# main.net
KiCad netlist of a schematic drawn in EAGLE
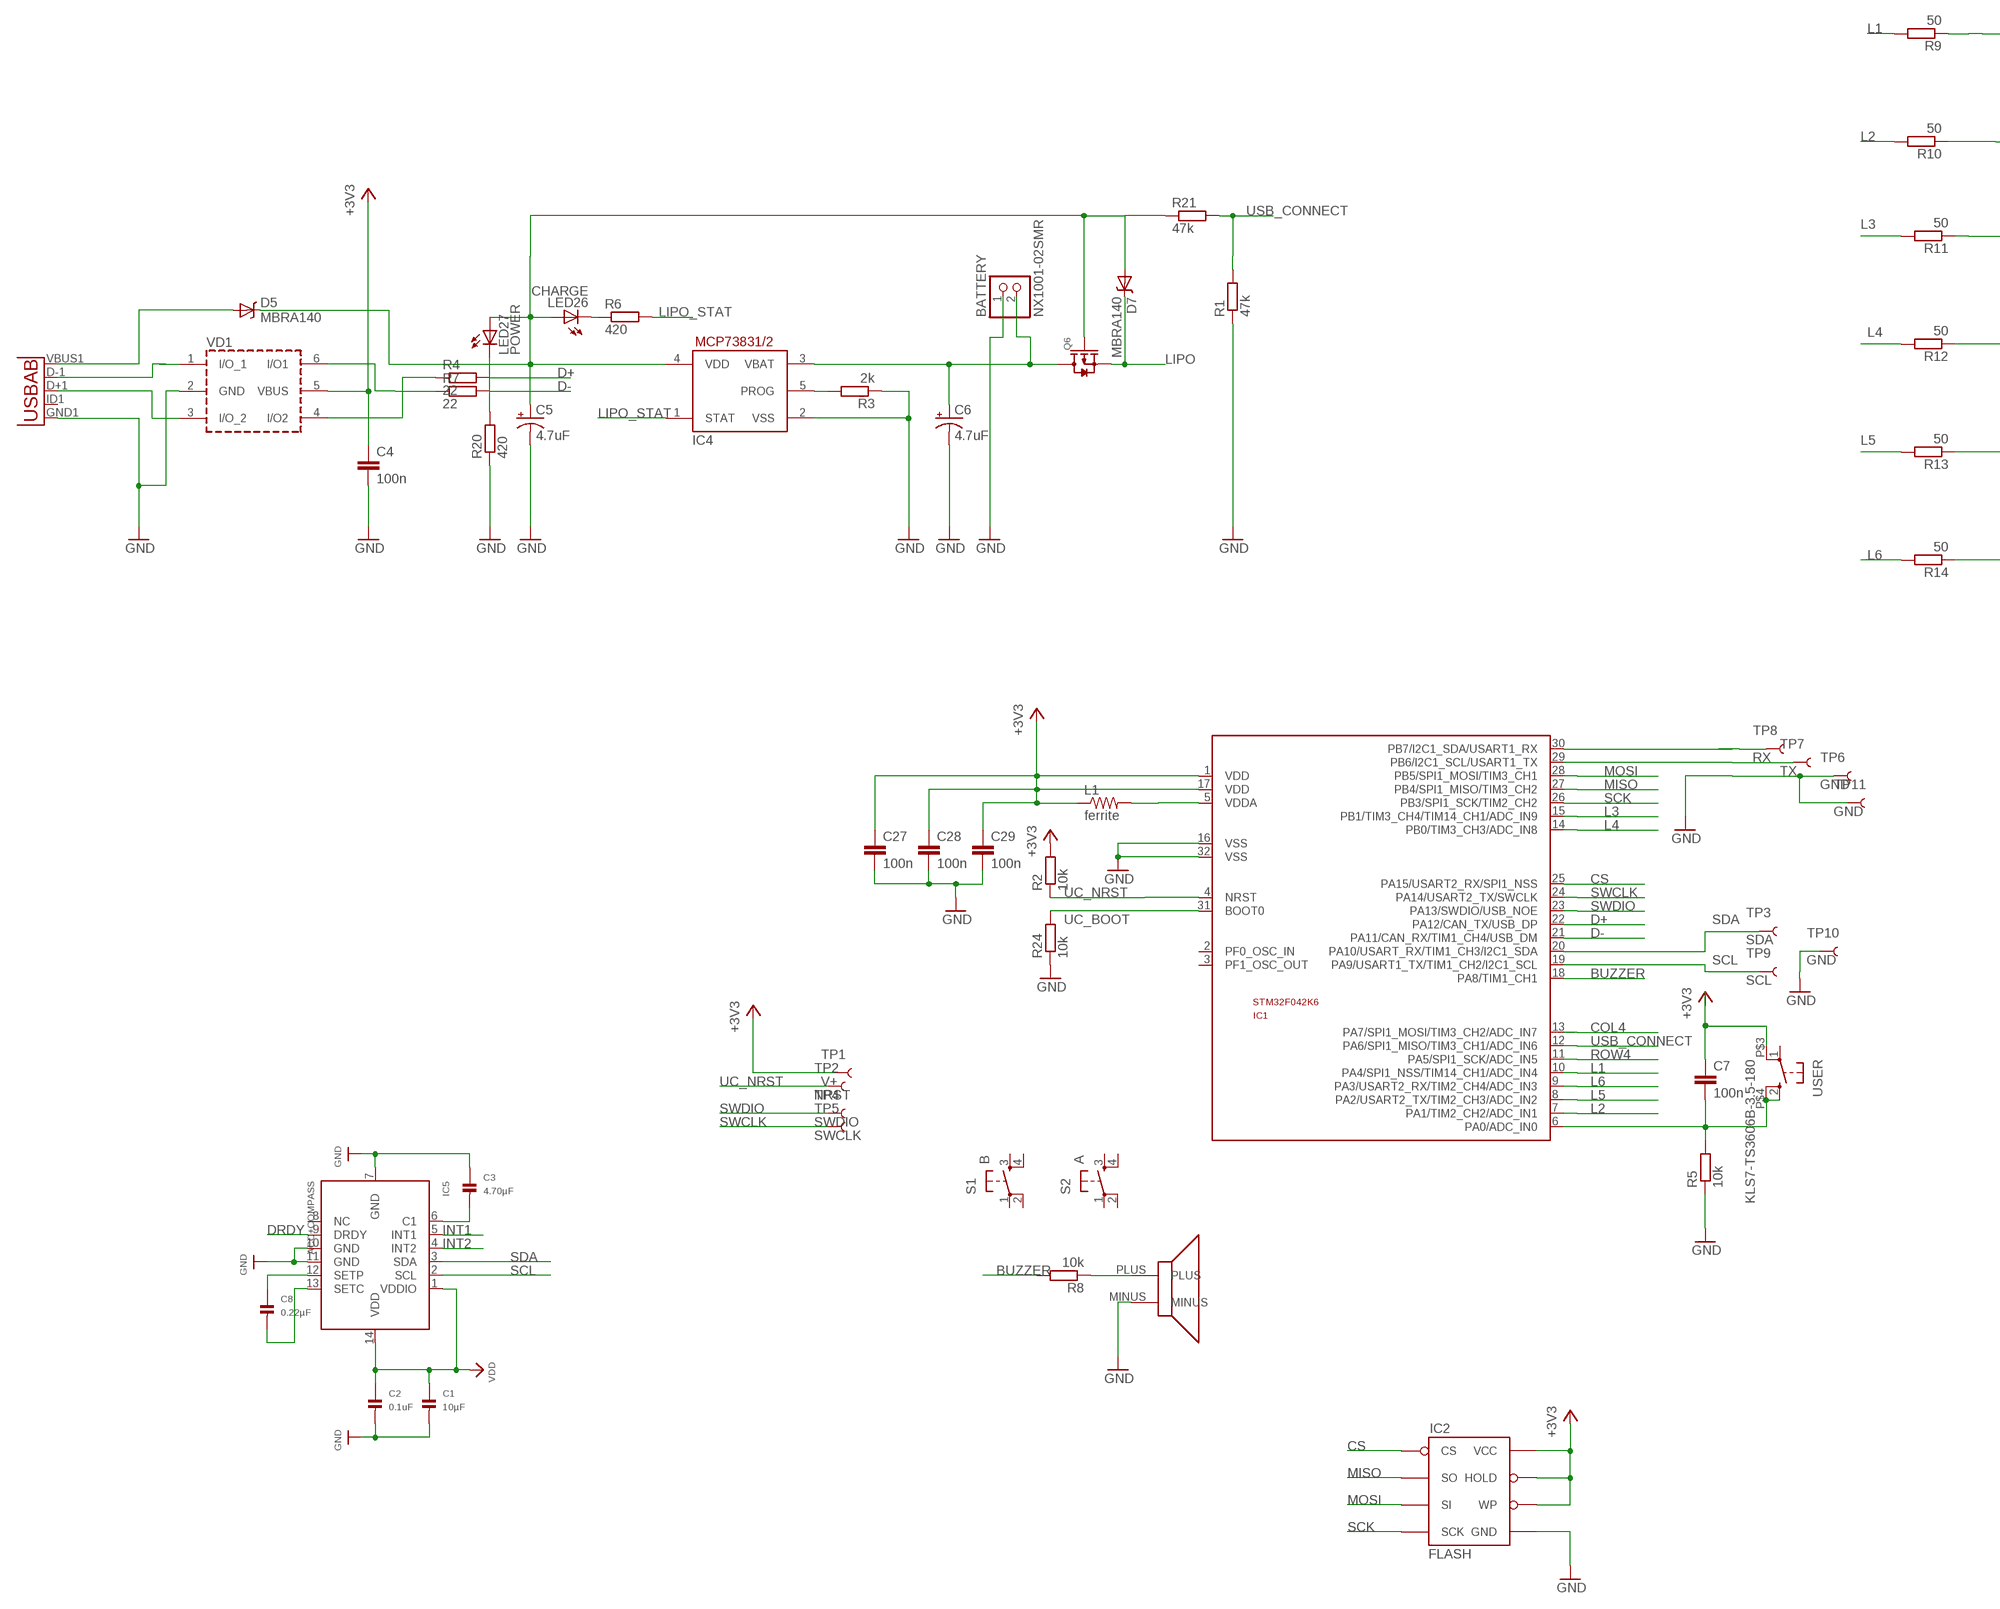
[diagram p0: schematic, sheet 1, part 1 of 2]
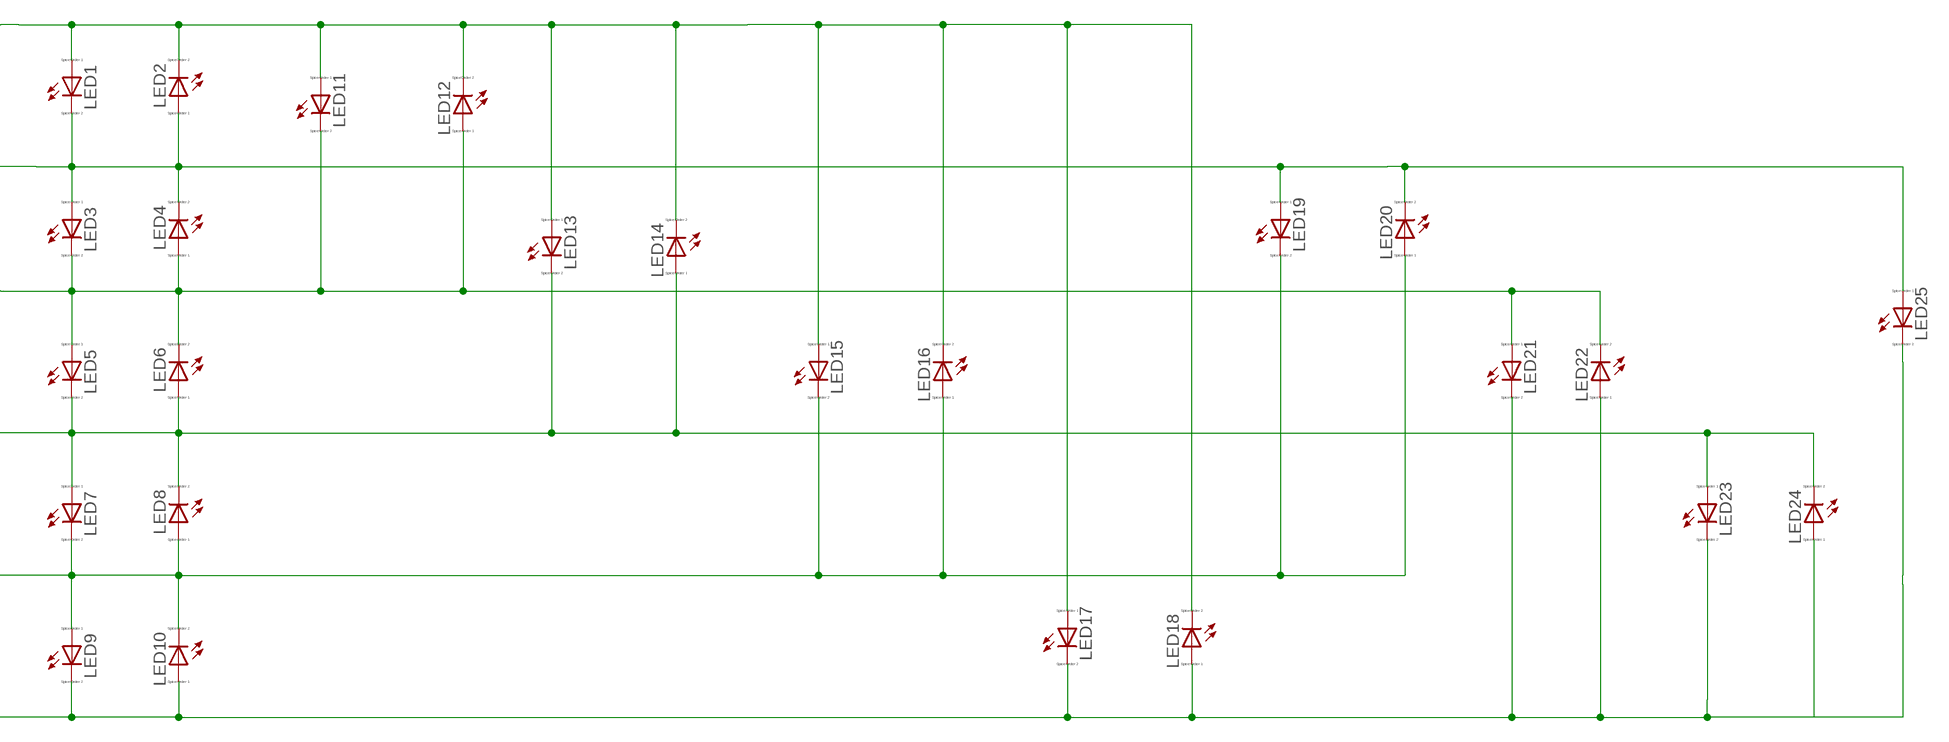
[diagram p1: schematic, sheet 1, part 2 of 2]

(export (version "E")
  (design (tool "Eeschema 10.0.6"))
  (components
    (comp (ref "BATTERY")
      (value "NX1001-02SMR")
      (footprint "eagle-import:NX1001-02")
      (libsource (lib "eagle-import") (part "NX1001-02SMR"))
    )
    (comp (ref "C1")
      (value "10µF")
      (footprint "eagle-import:_0805")
      (libsource (lib "eagle-import") (part "CAP_CERAMIC_0805"))
    )
    (comp (ref "C2")
      (value "0.1uF")
      (footprint "eagle-import:_0805")
      (libsource (lib "eagle-import") (part "CAP_CERAMIC_0805"))
    )
    (comp (ref "C3")
      (value "4.70µF")
      (footprint "eagle-import:_0805")
      (libsource (lib "eagle-import") (part "CAP_CERAMIC_0805"))
    )
    (comp (ref "C4")
      (value "100n")
      (footprint "eagle-import:C0603")
      (libsource (lib "eagle-import") (part "C-EUC0603"))
    )
    (comp (ref "C5")
      (value "4.7uF")
      (footprint "eagle-import:EIA3216")
      (libsource (lib "eagle-import") (part "CAP_POL1206"))
    )
    (comp (ref "C6")
      (value "4.7uF")
      (footprint "eagle-import:EIA3216")
      (libsource (lib "eagle-import") (part "CAP_POL1206"))
    )
    (comp (ref "C7")
      (value "100n")
      (footprint "eagle-import:C0603")
      (libsource (lib "eagle-import") (part "C-EUC0603"))
    )
    (comp (ref "C8")
      (value "0.22µF")
      (footprint "eagle-import:_0805")
      (libsource (lib "eagle-import") (part "CAP_CERAMIC_0805"))
    )
    (comp (ref "C27")
      (value "100n")
      (footprint "eagle-import:C0603")
      (libsource (lib "eagle-import") (part "C-EUC0603"))
    )
    (comp (ref "C28")
      (value "100n")
      (footprint "eagle-import:C0603")
      (libsource (lib "eagle-import") (part "C-EUC0603"))
    )
    (comp (ref "C29")
      (value "100n")
      (footprint "eagle-import:C0603")
      (libsource (lib "eagle-import") (part "C-EUC0603"))
    )
    (comp (ref "D5")
      (value "MBRA140")
      (footprint "eagle-import:SMA-DIODE")
      (libsource (lib "eagle-import") (part "MBRA140"))
    )
    (comp (ref "D7")
      (value "MBRA140")
      (footprint "eagle-import:SMA-DIODE")
      (fields (field (name "PROD_ID") "DIO-08053"))
      (libsource (lib "eagle-import") (part "MBRA140"))
    )
    (comp (ref "IC1")
      (value "STM32F042K6")
      (footprint "eagle-import:LQFP32-7X7")
      (libsource (lib "eagle-import") (part "STM32F042K6"))
    )
    (comp (ref "IC2")
      (value "FLASH")
      (footprint "eagle-import:SO08")
      (libsource (lib "eagle-import") (part "AT25DF041A-SSH-T"))
    )
    (comp (ref "IC4")
      (value "MCP73831")
      (footprint "eagle-import:SOT23-5L")
      (libsource (lib "eagle-import") (part "MCP73831/OT"))
    )
    (comp (ref "IC5")
      (value "ACC+COMPASS")
      (footprint "eagle-import:LGA14")
      (libsource (lib "eagle-import") (part "LSM303DLHC"))
    )
    (comp (ref "L1")
      (value "ferrite")
      (footprint "eagle-import:0603-RES")
      (libsource (lib "eagle-import") (part "220-5%"))
    )
    (comp (ref "LED1")
      (value "LED_ESML0603")
      (footprint "eagle-import:LED_SML0603")
      (libsource (lib "eagle-import") (part "LED_ESML0603"))
    )
    (comp (ref "LED2")
      (value "LED_ESML0603")
      (footprint "eagle-import:LED_SML0603")
      (libsource (lib "eagle-import") (part "LED_ESML0603"))
    )
    (comp (ref "LED3")
      (value "LED_ESML0603")
      (footprint "eagle-import:LED_SML0603")
      (libsource (lib "eagle-import") (part "LED_ESML0603"))
    )
    (comp (ref "LED4")
      (value "LED_ESML0603")
      (footprint "eagle-import:LED_SML0603")
      (libsource (lib "eagle-import") (part "LED_ESML0603"))
    )
    (comp (ref "LED5")
      (value "LED_ESML0603")
      (footprint "eagle-import:LED_SML0603")
      (libsource (lib "eagle-import") (part "LED_ESML0603"))
    )
    (comp (ref "LED6")
      (value "LED_ESML0603")
      (footprint "eagle-import:LED_SML0603")
      (libsource (lib "eagle-import") (part "LED_ESML0603"))
    )
    (comp (ref "LED7")
      (value "LED_ESML0603")
      (footprint "eagle-import:LED_SML0603")
      (libsource (lib "eagle-import") (part "LED_ESML0603"))
    )
    (comp (ref "LED8")
      (value "LED_ESML0603")
      (footprint "eagle-import:LED_SML0603")
      (libsource (lib "eagle-import") (part "LED_ESML0603"))
    )
    (comp (ref "LED9")
      (value "LED_ESML0603")
      (footprint "eagle-import:LED_SML0603")
      (libsource (lib "eagle-import") (part "LED_ESML0603"))
    )
    (comp (ref "LED10")
      (value "LED_ESML0603")
      (footprint "eagle-import:LED_SML0603")
      (libsource (lib "eagle-import") (part "LED_ESML0603"))
    )
    (comp (ref "LED11")
      (value "LED_ESML0603")
      (footprint "eagle-import:LED_SML0603")
      (libsource (lib "eagle-import") (part "LED_ESML0603"))
    )
    (comp (ref "LED12")
      (value "LED_ESML0603")
      (footprint "eagle-import:LED_SML0603")
      (libsource (lib "eagle-import") (part "LED_ESML0603"))
    )
    (comp (ref "LED13")
      (value "LED_ESML0603")
      (footprint "eagle-import:LED_SML0603")
      (libsource (lib "eagle-import") (part "LED_ESML0603"))
    )
    (comp (ref "LED14")
      (value "LED_ESML0603")
      (footprint "eagle-import:LED_SML0603")
      (libsource (lib "eagle-import") (part "LED_ESML0603"))
    )
    (comp (ref "LED15")
      (value "LED_ESML0603")
      (footprint "eagle-import:LED_SML0603")
      (libsource (lib "eagle-import") (part "LED_ESML0603"))
    )
    (comp (ref "LED16")
      (value "LED_ESML0603")
      (footprint "eagle-import:LED_SML0603")
      (libsource (lib "eagle-import") (part "LED_ESML0603"))
    )
    (comp (ref "LED17")
      (value "LED_ESML0603")
      (footprint "eagle-import:LED_SML0603")
      (libsource (lib "eagle-import") (part "LED_ESML0603"))
    )
    (comp (ref "LED18")
      (value "LED_ESML0603")
      (footprint "eagle-import:LED_SML0603")
      (libsource (lib "eagle-import") (part "LED_ESML0603"))
    )
    (comp (ref "LED19")
      (value "LED_ESML0603")
      (footprint "eagle-import:LED_SML0603")
      (libsource (lib "eagle-import") (part "LED_ESML0603"))
    )
    (comp (ref "LED20")
      (value "LED_ESML0603")
      (footprint "eagle-import:LED_SML0603")
      (libsource (lib "eagle-import") (part "LED_ESML0603"))
    )
    (comp (ref "LED21")
      (value "LED_ESML0603")
      (footprint "eagle-import:LED_SML0603")
      (libsource (lib "eagle-import") (part "LED_ESML0603"))
    )
    (comp (ref "LED22")
      (value "LED_ESML0603")
      (footprint "eagle-import:LED_SML0603")
      (libsource (lib "eagle-import") (part "LED_ESML0603"))
    )
    (comp (ref "LED23")
      (value "LED_ESML0603")
      (footprint "eagle-import:LED_SML0603")
      (libsource (lib "eagle-import") (part "LED_ESML0603"))
    )
    (comp (ref "LED24")
      (value "LED_ESML0603")
      (footprint "eagle-import:LED_SML0603")
      (libsource (lib "eagle-import") (part "LED_ESML0603"))
    )
    (comp (ref "LED25")
      (value "LED_ESML0603")
      (footprint "eagle-import:LED_SML0603")
      (libsource (lib "eagle-import") (part "LED_ESML0603"))
    )
    (comp (ref "LED26")
      (value "CHARGE")
      (footprint "eagle-import:CHIP-LED0805")
      (libsource (lib "eagle-import") (part "LEDCHIP-LED0805"))
    )
    (comp (ref "LED27")
      (value "POWER")
      (footprint "eagle-import:CHIP-LED0805")
      (libsource (lib "eagle-import") (part "LEDCHIP-LED0805"))
    )
    (comp (ref "Q6")
      (value "MOSFET-P-044021001")
      (footprint "eagle-import:SOT23")
      (libsource (lib "eagle-import") (part "MOSFET-P-044021001"))
    )
    (comp (ref "R1")
      (value "47k")
      (footprint "eagle-import:R0603")
      (libsource (lib "eagle-import") (part "R-EU_R0603"))
    )
    (comp (ref "R2")
      (value "10k")
      (footprint "eagle-import:R0603")
      (libsource (lib "eagle-import") (part "R-EU_R0603"))
    )
    (comp (ref "R3")
      (value "2k")
      (footprint "eagle-import:R0603")
      (libsource (lib "eagle-import") (part "R-EU_R0603"))
    )
    (comp (ref "R4")
      (value "22")
      (footprint "eagle-import:R0603")
      (libsource (lib "eagle-import") (part "R-EU_R0603"))
    )
    (comp (ref "R5")
      (value "10k")
      (footprint "eagle-import:R0603")
      (libsource (lib "eagle-import") (part "R-EU_R0603"))
    )
    (comp (ref "R6")
      (value "420")
      (footprint "eagle-import:R0603")
      (libsource (lib "eagle-import") (part "R-EU_R0603"))
    )
    (comp (ref "R7")
      (value "22")
      (footprint "eagle-import:R0603")
      (libsource (lib "eagle-import") (part "R-EU_R0603"))
    )
    (comp (ref "R8")
      (value "10k")
      (footprint "eagle-import:R0603")
      (libsource (lib "eagle-import") (part "R-EU_R0603"))
    )
    (comp (ref "R9")
      (value "50")
      (footprint "eagle-import:R0603")
      (libsource (lib "eagle-import") (part "R-EU_R0603"))
    )
    (comp (ref "R10")
      (value "50")
      (footprint "eagle-import:R0603")
      (libsource (lib "eagle-import") (part "R-EU_R0603"))
    )
    (comp (ref "R11")
      (value "50")
      (footprint "eagle-import:R0603")
      (libsource (lib "eagle-import") (part "R-EU_R0603"))
    )
    (comp (ref "R12")
      (value "50")
      (footprint "eagle-import:R0603")
      (libsource (lib "eagle-import") (part "R-EU_R0603"))
    )
    (comp (ref "R13")
      (value "50")
      (footprint "eagle-import:R0603")
      (libsource (lib "eagle-import") (part "R-EU_R0603"))
    )
    (comp (ref "R14")
      (value "50")
      (footprint "eagle-import:R0603")
      (libsource (lib "eagle-import") (part "R-EU_R0603"))
    )
    (comp (ref "R20")
      (value "420")
      (footprint "eagle-import:R0603")
      (libsource (lib "eagle-import") (part "R-EU_R0603"))
    )
    (comp (ref "R21")
      (value "47k")
      (footprint "eagle-import:R0603")
      (libsource (lib "eagle-import") (part "R-EU_R0603"))
    )
    (comp (ref "R24")
      (value "10k")
      (footprint "eagle-import:R0603")
      (libsource (lib "eagle-import") (part "R-EU_R0603"))
    )
    (comp (ref "S1")
      (value "B")
      (footprint "eagle-import:DTSM-6")
      (libsource (lib "eagle-import") (part "DTSM-6"))
    )
    (comp (ref "S2")
      (value "A")
      (footprint "eagle-import:DTSM-6")
      (libsource (lib "eagle-import") (part "DTSM-6"))
    )
    (comp (ref "TP1")
      (value "V+")
      (footprint "eagle-import:PAD.03X.05")
      (libsource (lib "eagle-import") (part "TEST-POINT3X5"))
    )
    (comp (ref "TP2")
      (value "NRST")
      (footprint "eagle-import:PAD.03X.05")
      (libsource (lib "eagle-import") (part "TEST-POINT3X5"))
    )
    (comp (ref "TP3")
      (value "SDA")
      (footprint "eagle-import:PAD.03X.05")
      (libsource (lib "eagle-import") (part "TEST-POINT3X5"))
    )
    (comp (ref "TP4")
      (value "SWDIO")
      (footprint "eagle-import:PAD.03X.05")
      (libsource (lib "eagle-import") (part "TEST-POINT3X5"))
    )
    (comp (ref "TP5")
      (value "SWCLK")
      (footprint "eagle-import:PAD.03X.05")
      (libsource (lib "eagle-import") (part "TEST-POINT3X5"))
    )
    (comp (ref "TP6")
      (value "GND")
      (footprint "eagle-import:PAD.03X.05")
      (libsource (lib "eagle-import") (part "TEST-POINT3X5"))
    )
    (comp (ref "TP7")
      (value "TX")
      (footprint "eagle-import:PAD.03X.05")
      (libsource (lib "eagle-import") (part "TEST-POINT3X5"))
    )
    (comp (ref "TP8")
      (value "RX")
      (footprint "eagle-import:PAD.03X.05")
      (libsource (lib "eagle-import") (part "TEST-POINT3X5"))
    )
    (comp (ref "TP9")
      (value "SCL")
      (footprint "eagle-import:PAD.03X.05")
      (libsource (lib "eagle-import") (part "TEST-POINT3X5"))
    )
    (comp (ref "TP10")
      (value "GND")
      (footprint "eagle-import:PAD.03X.05")
      (libsource (lib "eagle-import") (part "TEST-POINT3X5"))
    )
    (comp (ref "TP11")
      (value "GND")
      (footprint "eagle-import:PAD.03X.05")
      (libsource (lib "eagle-import") (part "TEST-POINT3X5"))
    )
    (comp (ref "U$1")
      (value "SMD-090045F-03627")
      (footprint "eagle-import:SMD090045F")
      (libsource (lib "eagle-import") (part "SMD-090045F-03627"))
    )
    (comp (ref "U2")
      (value "USB\"\"")
      (footprint "eagle-import:USB-MICRO-SMD")
      (libsource (lib "eagle-import") (part "USB{dblquote}{dblquote}"))
    )
    (comp (ref "USER")
      (value "KLS7-TS3606B-3.5-180")
      (footprint "eagle-import:KLS7-TS3606B")
      (libsource (lib "eagle-import") (part "KLS7-TS3606B-3.5-180"))
    )
    (comp (ref "VD1")
      (value "USBLC6-2SC6")
      (footprint "eagle-import:SOT-23-6L")
      (libsource (lib "eagle-import") (part "USBLC6-2SC6"))
    )
  )
  (nets
    (net (code "1") (name "+3V3") (class "Default")
      (node (ref "C27") (pin "1") (pinfunction "1_1") (pintype "passive"))
      (node (ref "C28") (pin "1") (pinfunction "1_1") (pintype "passive"))
      (node (ref "C29") (pin "1") (pinfunction "1_1") (pintype "passive"))
      (node (ref "C4") (pin "1") (pinfunction "1_1") (pintype "passive"))
      (node (ref "C7") (pin "1") (pinfunction "1_1") (pintype "passive"))
      (node (ref "IC1") (pin "1") (pinfunction "VDD_1") (pintype "power_in"))
      (node (ref "IC1") (pin "17") (pinfunction "VDD_17") (pintype "power_in"))
      (node (ref "IC2") (pin "3") (pinfunction "WP_3") (pintype "bidirectional"))
      (node (ref "IC2") (pin "7") (pinfunction "HOLD_7") (pintype "bidirectional"))
      (node (ref "IC2") (pin "8") (pinfunction "VCC_8") (pintype "bidirectional"))
      (node (ref "L1") (pin "1") (pinfunction "1_1") (pintype "passive"))
      (node (ref "R2") (pin "2") (pinfunction "2_2") (pintype "passive"))
      (node (ref "TP1") (pin "P$1") (pinfunction "1_P$1") (pintype "bidirectional"))
      (node (ref "USER") (pin "P$3") (pinfunction "2_P$3") (pintype "passive"))
      (node (ref "VD1") (pin "5") (pinfunction "VBUS_5") (pintype "bidirectional"))
    )
    (net (code "2") (name "/BUZZER") (class "Default")
      (node (ref "IC1") (pin "18") (pinfunction "PA8/TIM1_CH1_18") (pintype "bidirectional"))
      (node (ref "R8") (pin "2") (pinfunction "2_2") (pintype "passive"))
    )
    (net (code "3") (name "/COL4") (class "Default")
      (node (ref "IC1") (pin "13") (pinfunction "PA7/SPI1_MOSI/TIM3_CH2/ADC_IN7_13") (pintype "bidirectional"))
    )
    (net (code "4") (name "/CS") (class "Default")
      (node (ref "IC1") (pin "25") (pinfunction "PA15/USART2_RX/SPI1_NSS_25") (pintype "bidirectional"))
      (node (ref "IC2") (pin "1") (pinfunction "CS_1") (pintype "bidirectional"))
    )
    (net (code "5") (name "/D+") (class "Default")
      (node (ref "IC1") (pin "22") (pinfunction "PA12/CAN_TX/USB_DP_22") (pintype "bidirectional"))
      (node (ref "R4") (pin "2") (pinfunction "2_2") (pintype "passive"))
    )
    (net (code "6") (name "/D-") (class "Default")
      (node (ref "IC1") (pin "21") (pinfunction "PA11/CAN_RX/TIM1_CH4/USB_DM_21") (pintype "bidirectional"))
      (node (ref "R7") (pin "2") (pinfunction "2_2") (pintype "passive"))
    )
    (net (code "7") (name "/DRDY") (class "Default")
      (node (ref "IC5") (pin "9") (pinfunction "DRDY_9") (pintype "output"))
    )
    (net (code "8") (name "/INT1") (class "Default")
      (node (ref "IC5") (pin "5") (pinfunction "INT1_5") (pintype "output"))
    )
    (net (code "9") (name "/INT2") (class "Default")
      (node (ref "IC5") (pin "4") (pinfunction "INT2_4") (pintype "output"))
    )
    (net (code "10") (name "/L1") (class "Default")
      (node (ref "IC1") (pin "10") (pinfunction "PA4/SPI1_NSS/TIM14_CH1/ADC_IN4_10") (pintype "bidirectional"))
      (node (ref "R9") (pin "2") (pinfunction "2_2") (pintype "passive"))
    )
    (net (code "11") (name "/L2") (class "Default")
      (node (ref "IC1") (pin "7") (pinfunction "PA1/TIM2_CH2/ADC_IN1_7") (pintype "bidirectional"))
      (node (ref "R10") (pin "2") (pinfunction "2_2") (pintype "passive"))
    )
    (net (code "12") (name "/L3") (class "Default")
      (node (ref "IC1") (pin "15") (pinfunction "PB1/TIM3_CH4/TIM14_CH1/ADC_IN9_15") (pintype "bidirectional"))
      (node (ref "R11") (pin "2") (pinfunction "2_2") (pintype "passive"))
    )
    (net (code "13") (name "/L4") (class "Default")
      (node (ref "IC1") (pin "14") (pinfunction "PB0/TIM3_CH3/ADC_IN8_14") (pintype "bidirectional"))
      (node (ref "R12") (pin "2") (pinfunction "2_2") (pintype "passive"))
    )
    (net (code "14") (name "/L5") (class "Default")
      (node (ref "IC1") (pin "8") (pinfunction "PA2/USART2_TX/TIM2_CH3/ADC_IN2_8") (pintype "bidirectional"))
      (node (ref "R13") (pin "2") (pinfunction "2_2") (pintype "passive"))
    )
    (net (code "15") (name "/L6") (class "Default")
      (node (ref "IC1") (pin "9") (pinfunction "PA3/USART2_RX/TIM2_CH4/ADC_IN3_9") (pintype "bidirectional"))
      (node (ref "R14") (pin "2") (pinfunction "2_2") (pintype "passive"))
    )
    (net (code "16") (name "/LIPO") (class "Default")
      (node (ref "D7") (pin "C") (pinfunction "C_C") (pintype "passive"))
      (node (ref "Q6") (pin "2") (pinfunction "S_2") (pintype "passive"))
    )
    (net (code "17") (name "/LIPO_STAT") (class "Default")
      (node (ref "IC4") (pin "1") (pinfunction "STAT_1") (pintype "output"))
      (node (ref "R6") (pin "2") (pinfunction "2_2") (pintype "passive"))
    )
    (net (code "18") (name "/MISO") (class "Default")
      (node (ref "IC1") (pin "27") (pinfunction "PB4/SPI1_MISO/TIM3_CH2_27") (pintype "bidirectional"))
      (node (ref "IC2") (pin "2") (pinfunction "SO_2") (pintype "bidirectional"))
    )
    (net (code "19") (name "/MOSI") (class "Default")
      (node (ref "IC1") (pin "28") (pinfunction "PB5/SPI1_MOSI/TIM3_CH1_28") (pintype "bidirectional"))
      (node (ref "IC2") (pin "5") (pinfunction "SI_5") (pintype "bidirectional"))
    )
    (net (code "20") (name "/ROW4") (class "Default")
      (node (ref "IC1") (pin "11") (pinfunction "PA5/SPI1_SCK/ADC_IN5_11") (pintype "bidirectional"))
    )
    (net (code "21") (name "/SCK") (class "Default")
      (node (ref "IC1") (pin "26") (pinfunction "PB3/SPI1_SCK/TIM2_CH2_26") (pintype "bidirectional"))
      (node (ref "IC2") (pin "6") (pinfunction "SCK_6") (pintype "bidirectional"))
    )
    (net (code "22") (name "/SCL") (class "Default")
      (node (ref "IC1") (pin "19") (pinfunction "PA9/USART1_TX/TIM1_CH2/I2C1_SCL_19") (pintype "bidirectional"))
      (node (ref "IC5") (pin "2") (pinfunction "SCL_2") (pintype "bidirectional"))
      (node (ref "TP9") (pin "P$1") (pinfunction "1_P$1") (pintype "bidirectional"))
    )
    (net (code "23") (name "/SDA") (class "Default")
      (node (ref "IC1") (pin "20") (pinfunction "PA10/USART_RX/TIM1_CH3/I2C1_SDA_20") (pintype "bidirectional"))
      (node (ref "IC5") (pin "3") (pinfunction "SDA_3") (pintype "bidirectional"))
      (node (ref "TP3") (pin "P$1") (pinfunction "1_P$1") (pintype "bidirectional"))
    )
    (net (code "24") (name "/SWCLK") (class "Default")
      (node (ref "IC1") (pin "24") (pinfunction "PA14/USART2_TX/SWCLK_24") (pintype "bidirectional"))
      (node (ref "TP5") (pin "P$1") (pinfunction "1_P$1") (pintype "bidirectional"))
    )
    (net (code "25") (name "/SWDIO") (class "Default")
      (node (ref "IC1") (pin "23") (pinfunction "PA13/SWDIO/USB_NOE_23") (pintype "bidirectional"))
      (node (ref "TP4") (pin "P$1") (pinfunction "1_P$1") (pintype "bidirectional"))
    )
    (net (code "26") (name "/UC_BOOT") (class "Default")
      (node (ref "IC1") (pin "31") (pinfunction "BOOT0_31") (pintype "bidirectional"))
      (node (ref "R24") (pin "2") (pinfunction "2_2") (pintype "passive"))
    )
    (net (code "27") (name "/UC_NRST") (class "Default")
      (node (ref "IC1") (pin "4") (pinfunction "NRST_4") (pintype "bidirectional"))
      (node (ref "R2") (pin "1") (pinfunction "1_1") (pintype "passive"))
      (node (ref "TP2") (pin "P$1") (pinfunction "1_P$1") (pintype "bidirectional"))
    )
    (net (code "28") (name "/USB_CONNECT") (class "Default")
      (node (ref "IC1") (pin "12") (pinfunction "PA6/SPI1_MISO/TIM3_CH1/ADC_IN6_12") (pintype "bidirectional"))
      (node (ref "R1") (pin "2") (pinfunction "2_2") (pintype "passive"))
      (node (ref "R21") (pin "2") (pinfunction "2_2") (pintype "passive"))
    )
    (net (code "29") (name "GND") (class "Default")
      (node (ref "BATTERY") (pin "1") (pinfunction "1_1") (pintype "passive"))
      (node (ref "C1") (pin "2") (pinfunction "P$2_2") (pintype "passive"))
      (node (ref "C2") (pin "2") (pinfunction "P$2_2") (pintype "passive"))
      (node (ref "C27") (pin "2") (pinfunction "2_2") (pintype "passive"))
      (node (ref "C28") (pin "2") (pinfunction "2_2") (pintype "passive"))
      (node (ref "C29") (pin "2") (pinfunction "2_2") (pintype "passive"))
      (node (ref "C3") (pin "1") (pinfunction "P$1_1") (pintype "passive"))
      (node (ref "C4") (pin "2") (pinfunction "2_2") (pintype "passive"))
      (node (ref "C5") (pin "C") (pinfunction "-_C") (pintype "passive"))
      (node (ref "C6") (pin "C") (pinfunction "-_C") (pintype "passive"))
      (node (ref "IC1") (pin "16") (pinfunction "VSS_16") (pintype "power_in"))
      (node (ref "IC1") (pin "32") (pinfunction "VSS_32") (pintype "power_in"))
      (node (ref "IC2") (pin "4") (pinfunction "GND_4") (pintype "bidirectional"))
      (node (ref "IC4") (pin "2") (pinfunction "VSS_2") (pintype "power_in"))
      (node (ref "IC5") (pin "10") (pinfunction "GND_10") (pintype "power_in"))
      (node (ref "IC5") (pin "11") (pinfunction "GND_11") (pintype "power_in"))
      (node (ref "IC5") (pin "7") (pinfunction "GND_7") (pintype "power_in"))
      (node (ref "R1") (pin "1") (pinfunction "1_1") (pintype "passive"))
      (node (ref "R20") (pin "1") (pinfunction "1_1") (pintype "passive"))
      (node (ref "R24") (pin "1") (pinfunction "1_1") (pintype "passive"))
      (node (ref "R3") (pin "1") (pinfunction "1_1") (pintype "passive"))
      (node (ref "R5") (pin "1") (pinfunction "1_1") (pintype "passive"))
      (node (ref "TP10") (pin "P$1") (pinfunction "1_P$1") (pintype "bidirectional"))
      (node (ref "TP11") (pin "P$1") (pinfunction "1_P$1") (pintype "bidirectional"))
      (node (ref "TP6") (pin "P$1") (pinfunction "1_P$1") (pintype "bidirectional"))
      (node (ref "U$1") (pin "MINUS") (pinfunction "MINUS_MINUS") (pintype "bidirectional"))
      (node (ref "U2") (pin "GND1") (pinfunction "GND_GND1") (pintype "bidirectional"))
      (node (ref "VD1") (pin "2") (pinfunction "GND_2") (pintype "bidirectional"))
    )
    (net (code "30") (name "Net-(C3-P$2)") (class "Default")
      (node (ref "C3") (pin "2") (pinfunction "P$2_2") (pintype "passive"))
      (node (ref "IC5") (pin "6") (pinfunction "C1_6") (pintype "bidirectional"))
    )
    (net (code "31") (name "Net-(C5-+)") (class "Default")
      (node (ref "C5") (pin "A") (pinfunction "+_A") (pintype "passive"))
      (node (ref "D5") (pin "C") (pinfunction "C_C") (pintype "passive"))
      (node (ref "D7") (pin "A") (pinfunction "A_A") (pintype "passive"))
      (node (ref "IC4") (pin "4") (pinfunction "VDD_4") (pintype "power_in"))
      (node (ref "LED26") (pin "A") (pinfunction "A_A") (pintype "passive"))
      (node (ref "LED27") (pin "A") (pinfunction "A_A") (pintype "passive"))
      (node (ref "Q6") (pin "1") (pinfunction "G_1") (pintype "passive"))
      (node (ref "R21") (pin "1") (pinfunction "1_1") (pintype "passive"))
    )
    (net (code "32") (name "Net-(C6-+)") (class "Default")
      (node (ref "BATTERY") (pin "2") (pinfunction "2_2") (pintype "passive"))
      (node (ref "C6") (pin "A") (pinfunction "+_A") (pintype "passive"))
      (node (ref "IC4") (pin "3") (pinfunction "VBAT_3") (pintype "bidirectional"))
      (node (ref "Q6") (pin "3") (pinfunction "D_3") (pintype "passive"))
    )
    (net (code "33") (name "Net-(C8-P$1)") (class "Default")
      (node (ref "C8") (pin "1") (pinfunction "P$1_1") (pintype "passive"))
      (node (ref "IC5") (pin "12") (pinfunction "SETP_12") (pintype "bidirectional"))
    )
    (net (code "34") (name "Net-(C8-P$2)") (class "Default")
      (node (ref "C8") (pin "2") (pinfunction "P$2_2") (pintype "passive"))
      (node (ref "IC5") (pin "13") (pinfunction "SETC_13") (pintype "bidirectional"))
    )
    (net (code "35") (name "Net-(IC1-PA0{slash}ADC_IN0)") (class "Default")
      (node (ref "C7") (pin "2") (pinfunction "2_2") (pintype "passive"))
      (node (ref "IC1") (pin "6") (pinfunction "PA0/ADC_IN0_6") (pintype "bidirectional"))
      (node (ref "R5") (pin "2") (pinfunction "2_2") (pintype "passive"))
      (node (ref "USER") (pin "2") (pinfunction "3_2") (pintype "passive"))
      (node (ref "USER") (pin "P$4") (pinfunction "4_P$4") (pintype "passive"))
    )
    (net (code "36") (name "Net-(IC1-PB6{slash}I2C1_SCL{slash}USART1_TX)") (class "Default")
      (node (ref "IC1") (pin "29") (pinfunction "PB6/I2C1_SCL/USART1_TX_29") (pintype "bidirectional"))
      (node (ref "TP7") (pin "P$1") (pinfunction "1_P$1") (pintype "bidirectional"))
    )
    (net (code "37") (name "Net-(IC1-PB7{slash}I2C1_SDA{slash}USART1_RX)") (class "Default")
      (node (ref "IC1") (pin "30") (pinfunction "PB7/I2C1_SDA/USART1_RX_30") (pintype "bidirectional"))
      (node (ref "TP8") (pin "P$1") (pinfunction "1_P$1") (pintype "bidirectional"))
    )
    (net (code "38") (name "Net-(IC1-VDDA)") (class "Default")
      (node (ref "IC1") (pin "5") (pinfunction "VDDA_5") (pintype "power_in"))
      (node (ref "L1") (pin "2") (pinfunction "2_2") (pintype "passive"))
    )
    (net (code "39") (name "Net-(IC4-PROG)") (class "Default")
      (node (ref "IC4") (pin "5") (pinfunction "PROG_5") (pintype "input"))
      (node (ref "R3") (pin "2") (pinfunction "2_2") (pintype "passive"))
    )
    (net (code "40") (name "Net-(LED1-PadA)") (class "Default")
      (node (ref "LED1") (pin "A") (pinfunction "A_A") (pintype "passive"))
      (node (ref "LED11") (pin "A") (pinfunction "A_A") (pintype "passive"))
      (node (ref "LED12") (pin "C") (pinfunction "C_C") (pintype "passive"))
      (node (ref "LED13") (pin "A") (pinfunction "A_A") (pintype "passive"))
      (node (ref "LED14") (pin "C") (pinfunction "C_C") (pintype "passive"))
      (node (ref "LED15") (pin "A") (pinfunction "A_A") (pintype "passive"))
      (node (ref "LED16") (pin "C") (pinfunction "C_C") (pintype "passive"))
      (node (ref "LED17") (pin "A") (pinfunction "A_A") (pintype "passive"))
      (node (ref "LED18") (pin "C") (pinfunction "C_C") (pintype "passive"))
      (node (ref "LED2") (pin "C") (pinfunction "C_C") (pintype "passive"))
      (node (ref "R9") (pin "1") (pinfunction "1_1") (pintype "passive"))
    )
    (net (code "41") (name "Net-(LED1-PadC)") (class "Default")
      (node (ref "LED1") (pin "C") (pinfunction "C_C") (pintype "passive"))
      (node (ref "LED19") (pin "A") (pinfunction "A_A") (pintype "passive"))
      (node (ref "LED2") (pin "A") (pinfunction "A_A") (pintype "passive"))
      (node (ref "LED20") (pin "C") (pinfunction "C_C") (pintype "passive"))
      (node (ref "LED25") (pin "A") (pinfunction "A_A") (pintype "passive"))
      (node (ref "LED3") (pin "A") (pinfunction "A_A") (pintype "passive"))
      (node (ref "LED4") (pin "C") (pinfunction "C_C") (pintype "passive"))
      (node (ref "R10") (pin "1") (pinfunction "1_1") (pintype "passive"))
    )
    (net (code "42") (name "Net-(LED10-PadA)") (class "Default")
      (node (ref "LED10") (pin "A") (pinfunction "A_A") (pintype "passive"))
      (node (ref "LED17") (pin "C") (pinfunction "C_C") (pintype "passive"))
      (node (ref "LED18") (pin "A") (pinfunction "A_A") (pintype "passive"))
      (node (ref "LED21") (pin "C") (pinfunction "C_C") (pintype "passive"))
      (node (ref "LED22") (pin "A") (pinfunction "A_A") (pintype "passive"))
      (node (ref "LED23") (pin "C") (pinfunction "C_C") (pintype "passive"))
      (node (ref "LED24") (pin "A") (pinfunction "A_A") (pintype "passive"))
      (node (ref "LED25") (pin "C") (pinfunction "C_C") (pintype "passive"))
      (node (ref "LED9") (pin "C") (pinfunction "C_C") (pintype "passive"))
      (node (ref "R14") (pin "1") (pinfunction "1_1") (pintype "passive"))
    )
    (net (code "43") (name "Net-(LED10-PadC)") (class "Default")
      (node (ref "LED10") (pin "C") (pinfunction "C_C") (pintype "passive"))
      (node (ref "LED15") (pin "C") (pinfunction "C_C") (pintype "passive"))
      (node (ref "LED16") (pin "A") (pinfunction "A_A") (pintype "passive"))
      (node (ref "LED19") (pin "C") (pinfunction "C_C") (pintype "passive"))
      (node (ref "LED20") (pin "A") (pinfunction "A_A") (pintype "passive"))
      (node (ref "LED7") (pin "C") (pinfunction "C_C") (pintype "passive"))
      (node (ref "LED8") (pin "A") (pinfunction "A_A") (pintype "passive"))
      (node (ref "LED9") (pin "A") (pinfunction "A_A") (pintype "passive"))
      (node (ref "R13") (pin "1") (pinfunction "1_1") (pintype "passive"))
    )
    (net (code "44") (name "Net-(LED11-PadC)") (class "Default")
      (node (ref "LED11") (pin "C") (pinfunction "C_C") (pintype "passive"))
      (node (ref "LED12") (pin "A") (pinfunction "A_A") (pintype "passive"))
      (node (ref "LED21") (pin "A") (pinfunction "A_A") (pintype "passive"))
      (node (ref "LED22") (pin "C") (pinfunction "C_C") (pintype "passive"))
      (node (ref "LED3") (pin "C") (pinfunction "C_C") (pintype "passive"))
      (node (ref "LED4") (pin "A") (pinfunction "A_A") (pintype "passive"))
      (node (ref "LED5") (pin "A") (pinfunction "A_A") (pintype "passive"))
      (node (ref "LED6") (pin "C") (pinfunction "C_C") (pintype "passive"))
      (node (ref "R11") (pin "1") (pinfunction "1_1") (pintype "passive"))
    )
    (net (code "45") (name "Net-(LED13-PadC)") (class "Default")
      (node (ref "LED13") (pin "C") (pinfunction "C_C") (pintype "passive"))
      (node (ref "LED14") (pin "A") (pinfunction "A_A") (pintype "passive"))
      (node (ref "LED23") (pin "A") (pinfunction "A_A") (pintype "passive"))
      (node (ref "LED24") (pin "C") (pinfunction "C_C") (pintype "passive"))
      (node (ref "LED5") (pin "C") (pinfunction "C_C") (pintype "passive"))
      (node (ref "LED6") (pin "A") (pinfunction "A_A") (pintype "passive"))
      (node (ref "LED7") (pin "A") (pinfunction "A_A") (pintype "passive"))
      (node (ref "LED8") (pin "C") (pinfunction "C_C") (pintype "passive"))
      (node (ref "R12") (pin "1") (pinfunction "1_1") (pintype "passive"))
    )
    (net (code "46") (name "Net-(LED26-PadC)") (class "Default")
      (node (ref "LED26") (pin "C") (pinfunction "C_C") (pintype "passive"))
      (node (ref "R6") (pin "1") (pinfunction "1_1") (pintype "passive"))
    )
    (net (code "47") (name "Net-(LED27-PadC)") (class "Default")
      (node (ref "LED27") (pin "C") (pinfunction "C_C") (pintype "passive"))
      (node (ref "R20") (pin "2") (pinfunction "2_2") (pintype "passive"))
    )
    (net (code "48") (name "Net-(R8-Pad1)") (class "Default")
      (node (ref "R8") (pin "1") (pinfunction "1_1") (pintype "passive"))
      (node (ref "U$1") (pin "PLUS") (pinfunction "PLUS_PLUS") (pintype "bidirectional"))
    )
    (net (code "49") (name "Net-(U2-D+)") (class "Default")
      (node (ref "U2") (pin "D+1") (pinfunction "D+_D+1") (pintype "bidirectional"))
      (node (ref "VD1") (pin "3") (pinfunction "I/O_2_3") (pintype "bidirectional"))
    )
    (net (code "50") (name "Net-(U2-D-)") (class "Default")
      (node (ref "U2") (pin "D-1") (pinfunction "D-_D-1") (pintype "bidirectional"))
      (node (ref "VD1") (pin "1") (pinfunction "I/O_1_1") (pintype "bidirectional"))
    )
    (net (code "51") (name "Net-(U2-VBUS)") (class "Default")
      (node (ref "D5") (pin "A") (pinfunction "A_A") (pintype "passive"))
      (node (ref "U2") (pin "VBUS1") (pinfunction "VBUS_VBUS1") (pintype "bidirectional"))
    )
    (net (code "52") (name "Net-(VD1-I{slash}O1)") (class "Default")
      (node (ref "R7") (pin "1") (pinfunction "1_1") (pintype "passive"))
      (node (ref "VD1") (pin "6") (pinfunction "I/O1_6") (pintype "bidirectional"))
    )
    (net (code "53") (name "Net-(VD1-I{slash}O2)") (class "Default")
      (node (ref "R4") (pin "1") (pinfunction "1_1") (pintype "passive"))
      (node (ref "VD1") (pin "4") (pinfunction "I/O2_4") (pintype "bidirectional"))
    )
    (net (code "54") (name "VDD") (class "Default")
      (node (ref "C1") (pin "1") (pinfunction "P$1_1") (pintype "passive"))
      (node (ref "C2") (pin "1") (pinfunction "P$1_1") (pintype "passive"))
      (node (ref "IC5") (pin "1") (pinfunction "VDDIO_1") (pintype "power_in"))
      (node (ref "IC5") (pin "14") (pinfunction "VDD_14") (pintype "power_in"))
    )
    (net (code "55") (name "unconnected-(IC1-PF0_OSC_IN-Pad2)") (class "Default")
      (node (ref "IC1") (pin "2") (pinfunction "PF0_OSC_IN_2") (pintype "bidirectional"))
    )
    (net (code "56") (name "unconnected-(IC1-PF1_OSC_OUT-Pad3)") (class "Default")
      (node (ref "IC1") (pin "3") (pinfunction "PF1_OSC_OUT_3") (pintype "bidirectional"))
    )
    (net (code "57") (name "unconnected-(IC5-NC-Pad8)") (class "Default")
      (node (ref "IC5") (pin "8") (pinfunction "NC_8") (pintype "bidirectional"))
    )
    (net (code "58") (name "unconnected-(S1-Pad1)") (class "Default")
      (node (ref "S1") (pin "1") (pinfunction "1_1") (pintype "passive"))
    )
    (net (code "59") (name "unconnected-(S1-Pad2)") (class "Default")
      (node (ref "S1") (pin "2") (pinfunction "2_2") (pintype "passive"))
    )
    (net (code "60") (name "unconnected-(S1-Pad3)") (class "Default")
      (node (ref "S1") (pin "3") (pinfunction "3_3") (pintype "passive"))
    )
    (net (code "61") (name "unconnected-(S1-Pad4)") (class "Default")
      (node (ref "S1") (pin "4") (pinfunction "4_4") (pintype "passive"))
    )
    (net (code "62") (name "unconnected-(S2-Pad1)") (class "Default")
      (node (ref "S2") (pin "1") (pinfunction "1_1") (pintype "passive"))
    )
    (net (code "63") (name "unconnected-(S2-Pad2)") (class "Default")
      (node (ref "S2") (pin "2") (pinfunction "2_2") (pintype "passive"))
    )
    (net (code "64") (name "unconnected-(S2-Pad3)") (class "Default")
      (node (ref "S2") (pin "3") (pinfunction "3_3") (pintype "passive"))
    )
    (net (code "65") (name "unconnected-(S2-Pad4)") (class "Default")
      (node (ref "S2") (pin "4") (pinfunction "4_4") (pintype "passive"))
    )
    (net (code "66") (name "unconnected-(U2-USBID-PadID1)") (class "Default")
      (node (ref "U2") (pin "ID1") (pinfunction "USBID_ID1") (pintype "bidirectional"))
    )
    (net (code "67") (name "unconnected-(USER-Pad1)") (class "Default")
      (node (ref "USER") (pin "1") (pinfunction "1_1") (pintype "passive"))
    )
  )
)
